# altium_import_netname.net
KiCad netlist of a schematic drawn in Altium Designer
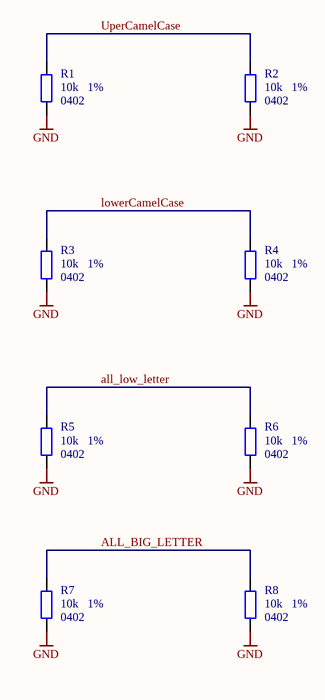
[diagram p0: altium_import_netname.SchDoc]

(export (version "E")
  (design (tool "Eeschema 10.0.6"))
  (components
    (comp (ref "R1")
      (value "10k")
      (footprint "CRCW0402")
      (description "0.063W, 0402, 1%, 10k, 50 V")
      (fields
        (field (name "MANUFACTURER") "Vishay")
        (field (name "VOLTAGE") "50 V")
        (field (name "TOLERANCE") "1%")
        (field (name "PACKAGE") "0402")
      )
      (libsource (lib "Widerstand 0402") (part "CRCW040210K0FKED"))
    )
    (comp (ref "R2")
      (value "10k")
      (footprint "CRCW0402")
      (description "0.063W, 0402, 1%, 10k, 50 V")
      (fields
        (field (name "MANUFACTURER") "Vishay")
        (field (name "VOLTAGE") "50 V")
        (field (name "TOLERANCE") "1%")
        (field (name "PACKAGE") "0402")
      )
      (libsource (lib "Widerstand 0402") (part "CRCW040210K0FKED"))
    )
    (comp (ref "R3")
      (value "10k")
      (footprint "CRCW0402")
      (description "0.063W, 0402, 1%, 10k, 50 V")
      (fields
        (field (name "MANUFACTURER") "Vishay")
        (field (name "VOLTAGE") "50 V")
        (field (name "TOLERANCE") "1%")
        (field (name "PACKAGE") "0402")
      )
      (libsource (lib "Widerstand 0402") (part "CRCW040210K0FKED"))
    )
    (comp (ref "R4")
      (value "10k")
      (footprint "CRCW0402")
      (description "0.063W, 0402, 1%, 10k, 50 V")
      (fields
        (field (name "MANUFACTURER") "Vishay")
        (field (name "VOLTAGE") "50 V")
        (field (name "TOLERANCE") "1%")
        (field (name "PACKAGE") "0402")
      )
      (libsource (lib "Widerstand 0402") (part "CRCW040210K0FKED"))
    )
    (comp (ref "R5")
      (value "10k")
      (footprint "CRCW0402")
      (description "0.063W, 0402, 1%, 10k, 50 V")
      (fields
        (field (name "MANUFACTURER") "Vishay")
        (field (name "VOLTAGE") "50 V")
        (field (name "TOLERANCE") "1%")
        (field (name "PACKAGE") "0402")
      )
      (libsource (lib "Widerstand 0402") (part "CRCW040210K0FKED"))
    )
    (comp (ref "R6")
      (value "10k")
      (footprint "CRCW0402")
      (description "0.063W, 0402, 1%, 10k, 50 V")
      (fields
        (field (name "MANUFACTURER") "Vishay")
        (field (name "VOLTAGE") "50 V")
        (field (name "TOLERANCE") "1%")
        (field (name "PACKAGE") "0402")
      )
      (libsource (lib "Widerstand 0402") (part "CRCW040210K0FKED"))
    )
    (comp (ref "R7")
      (value "10k")
      (footprint "CRCW0402")
      (description "0.063W, 0402, 1%, 10k, 50 V")
      (fields
        (field (name "MANUFACTURER") "Vishay")
        (field (name "VOLTAGE") "50 V")
        (field (name "TOLERANCE") "1%")
        (field (name "PACKAGE") "0402")
      )
      (libsource (lib "Widerstand 0402") (part "CRCW040210K0FKED"))
    )
    (comp (ref "R8")
      (value "10k")
      (footprint "CRCW0402")
      (description "0.063W, 0402, 1%, 10k, 50 V")
      (fields
        (field (name "MANUFACTURER") "Vishay")
        (field (name "VOLTAGE") "50 V")
        (field (name "TOLERANCE") "1%")
        (field (name "PACKAGE") "0402")
      )
      (libsource (lib "Widerstand 0402") (part "CRCW040210K0FKED"))
    )
  )
  (nets
    (net (code "1") (name "/ALL_BIG_LETTER") (class "Default")
      (node (ref "R7") (pin "2") (pintype "passive"))
      (node (ref "R8") (pin "2") (pintype "passive"))
    )
    (net (code "2") (name "/UperCamelCase") (class "Default")
      (node (ref "R1") (pin "2") (pintype "passive"))
      (node (ref "R2") (pin "2") (pintype "passive"))
    )
    (net (code "3") (name "/all_low_letter") (class "Default")
      (node (ref "R5") (pin "2") (pintype "passive"))
      (node (ref "R6") (pin "2") (pintype "passive"))
    )
    (net (code "4") (name "/lowerCamelCase") (class "Default")
      (node (ref "R3") (pin "2") (pintype "passive"))
      (node (ref "R4") (pin "2") (pintype "passive"))
    )
    (net (code "5") (name "GND") (class "Default")
      (node (ref "R1") (pin "1") (pintype "passive"))
      (node (ref "R2") (pin "1") (pintype "passive"))
      (node (ref "R3") (pin "1") (pintype "passive"))
      (node (ref "R4") (pin "1") (pintype "passive"))
      (node (ref "R5") (pin "1") (pintype "passive"))
      (node (ref "R6") (pin "1") (pintype "passive"))
      (node (ref "R7") (pin "1") (pintype "passive"))
      (node (ref "R8") (pin "1") (pintype "passive"))
    )
  )
)
